# Sheet2.net
KiCad netlist of a schematic drawn in Altium Designer
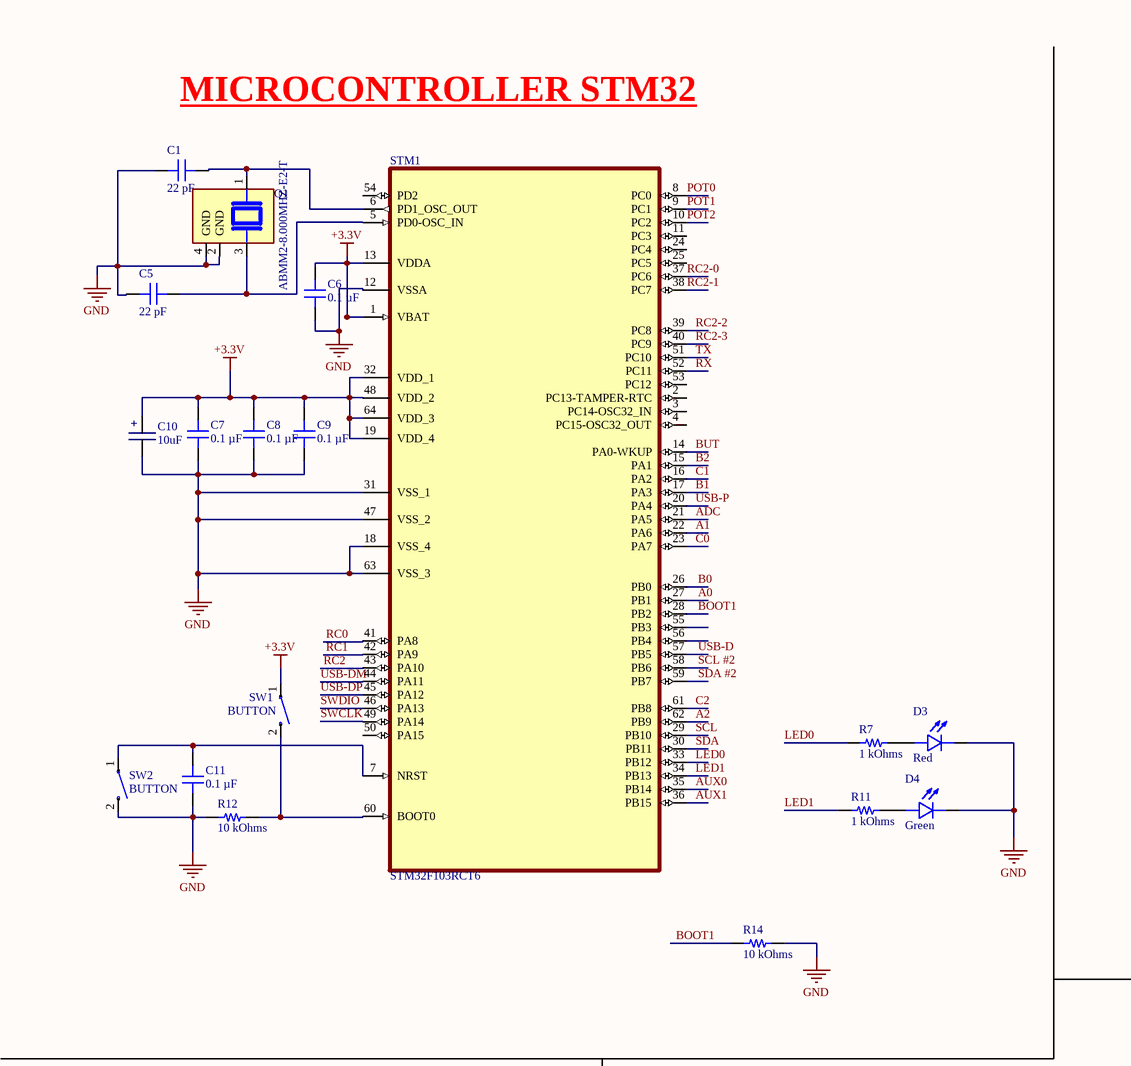
[diagram p0: Sheet2.SchDoc, top left]
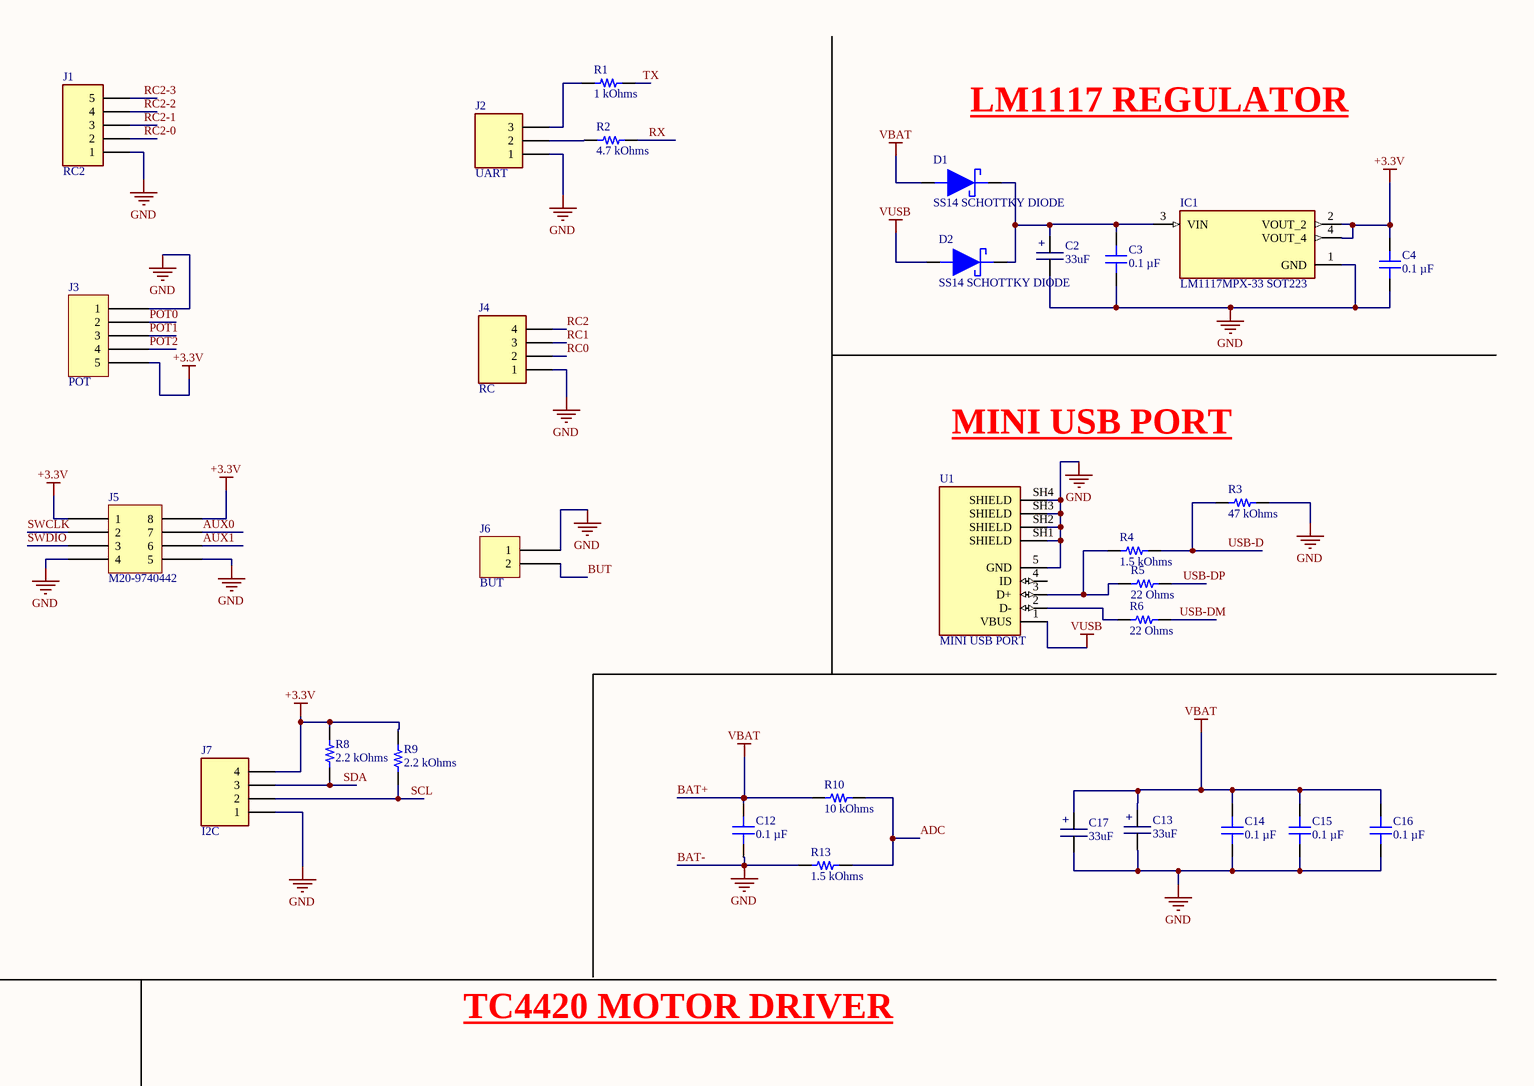
[diagram p1: Sheet2.SchDoc, top right]
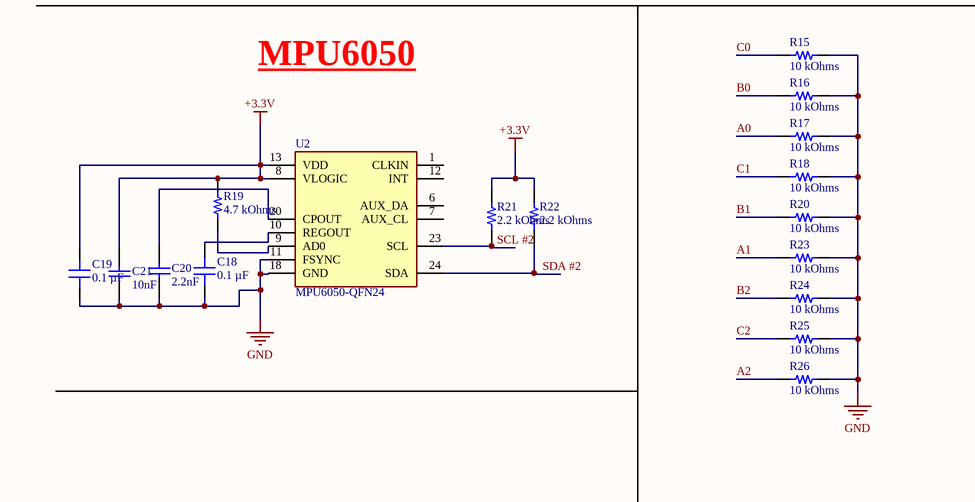
[diagram p2: Sheet2.SchDoc, bottom left]
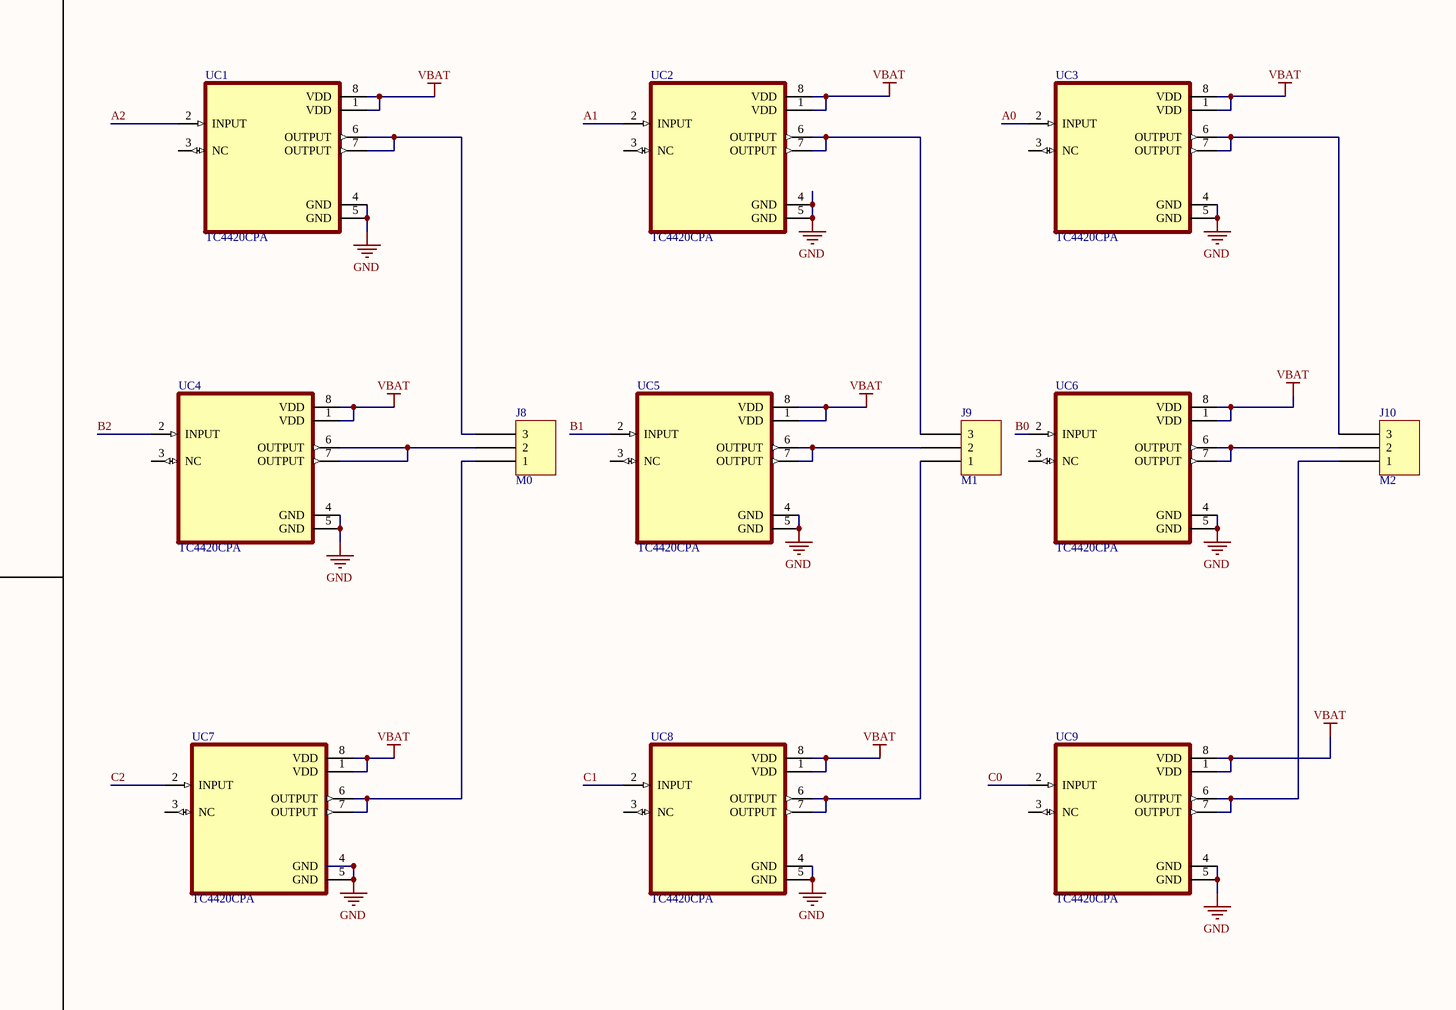
[diagram p3: Sheet2.SchDoc, bottom right]

(export (version "E")
  (design (tool "Eeschema 10.0.6"))
  (components
    (comp (ref "C1")
      (value "22 pF")
      (footprint "CAP 1206_3216 - 0.8MM")
      (description "CAP CER 22PF 50V C0G/NPO 1206")
      (fields
        (field (name "PART NUMBER") "CC1206JRNPO9BN220")
        (field (name "CAPACITANCE") "22 pF")
        (field (name "MANUFACTURER") "Yageo")
      )
      (libsource (lib "Celestial Altium Library - altium_library") (part "Capacitor"))
    )
    (comp (ref "C2")
      (value "33uF")
      (footprint "TANTAL CAP C-CASE")
      (libsource (lib "My_Library") (part "TANTAL CAP C-CASE"))
    )
    (comp (ref "C3")
      (value "0.1 µF")
      (footprint "CAP 1206_3216 - 0.8MM")
      (description "MLCC 1206 100V 100NF X7R")
      (fields
        (field (name "PART NUMBER") "1206B104J101N")
        (field (name "CAPACITANCE") "0.1 µF")
        (field (name "MANUFACTURER") "Knowles Novacap")
      )
      (libsource (lib "Celestial Altium Library - altium_library") (part "Capacitor"))
    )
    (comp (ref "C4")
      (value "0.1 µF")
      (footprint "CAP 1206_3216 - 0.8MM")
      (description "MLCC 1206 100V 100NF X7R")
      (fields
        (field (name "PART NUMBER") "1206B104J101N")
        (field (name "CAPACITANCE") "0.1 µF")
        (field (name "MANUFACTURER") "Knowles Novacap")
      )
      (libsource (lib "Celestial Altium Library - altium_library") (part "Capacitor"))
    )
    (comp (ref "C5")
      (value "22 pF")
      (footprint "CAP 1206_3216 - 0.8MM")
      (description "CAP CER 22PF 50V C0G/NPO 1206")
      (fields
        (field (name "PART NUMBER") "CC1206JRNPO9BN220")
        (field (name "CAPACITANCE") "22 pF")
        (field (name "MANUFACTURER") "Yageo")
      )
      (libsource (lib "Celestial Altium Library - altium_library") (part "Capacitor"))
    )
    (comp (ref "C6")
      (value "0.1 µF")
      (footprint "CAP 1206_3216 - 0.8MM")
      (description "MLCC 1206 100V 100NF X7R")
      (fields
        (field (name "PART NUMBER") "1206B104J101N")
        (field (name "CAPACITANCE") "0.1 µF")
        (field (name "MANUFACTURER") "Knowles Novacap")
      )
      (libsource (lib "Celestial Altium Library - altium_library") (part "Capacitor"))
    )
    (comp (ref "C7")
      (value "0.1 µF")
      (footprint "CAP 1206_3216 - 0.8MM")
      (description "MLCC 1206 100V 100NF X7R")
      (fields
        (field (name "PART NUMBER") "1206B104J101N")
        (field (name "CAPACITANCE") "0.1 µF")
        (field (name "MANUFACTURER") "Knowles Novacap")
      )
      (libsource (lib "Celestial Altium Library - altium_library") (part "Capacitor"))
    )
    (comp (ref "C8")
      (value "0.1 µF")
      (footprint "CAP 1206_3216 - 0.8MM")
      (description "MLCC 1206 100V 100NF X7R")
      (fields
        (field (name "PART NUMBER") "1206B104J101N")
        (field (name "CAPACITANCE") "0.1 µF")
        (field (name "MANUFACTURER") "Knowles Novacap")
      )
      (libsource (lib "Celestial Altium Library - altium_library") (part "Capacitor"))
    )
    (comp (ref "C9")
      (value "0.1 µF")
      (footprint "CAP 1206_3216 - 0.8MM")
      (description "MLCC 1206 100V 100NF X7R")
      (fields
        (field (name "PART NUMBER") "1206B104J101N")
        (field (name "CAPACITANCE") "0.1 µF")
        (field (name "MANUFACTURER") "Knowles Novacap")
      )
      (libsource (lib "Celestial Altium Library - altium_library") (part "Capacitor"))
    )
    (comp (ref "C10")
      (value "10uF")
      (footprint "TANTALUM SMD B")
      (description "Generic Tantalum Type B, 3.5x2.8x1.9.")
      (libsource (lib "Tantalum Capacitor") (part "TANTALUM SMD B"))
    )
    (comp (ref "C11")
      (value "0.1 µF")
      (footprint "CAP 1206_3216 - 0.8MM")
      (description "MLCC 1206 100V 100NF X7R")
      (fields
        (field (name "PART NUMBER") "1206B104J101N")
        (field (name "CAPACITANCE") "0.1 µF")
        (field (name "MANUFACTURER") "Knowles Novacap")
      )
      (libsource (lib "Celestial Altium Library - altium_library") (part "Capacitor"))
    )
    (comp (ref "C12")
      (value "0.1 µF")
      (footprint "CAP 1206_3216 - 0.8MM")
      (description "MLCC 1206 100V 100NF X7R")
      (fields
        (field (name "PART NUMBER") "1206B104J101N")
        (field (name "CAPACITANCE") "0.1 µF")
        (field (name "MANUFACTURER") "Knowles Novacap")
      )
      (libsource (lib "Celestial Altium Library - altium_library") (part "Capacitor"))
    )
    (comp (ref "C13")
      (value "33uF")
      (footprint "TANTAL CAP C-CASE")
      (libsource (lib "My_Library") (part "TANTAL CAP C-CASE"))
    )
    (comp (ref "C14")
      (value "0.1 µF")
      (footprint "CAP 1206_3216 - 0.8MM")
      (description "MLCC 1206 100V 100NF X7R")
      (fields
        (field (name "PART NUMBER") "1206B104J101N")
        (field (name "CAPACITANCE") "0.1 µF")
        (field (name "MANUFACTURER") "Knowles Novacap")
      )
      (libsource (lib "Celestial Altium Library - altium_library") (part "Capacitor"))
    )
    (comp (ref "C15")
      (value "0.1 µF")
      (footprint "CAP 1206_3216 - 0.8MM")
      (description "MLCC 1206 100V 100NF X7R")
      (fields
        (field (name "PART NUMBER") "1206B104J101N")
        (field (name "CAPACITANCE") "0.1 µF")
        (field (name "MANUFACTURER") "Knowles Novacap")
      )
      (libsource (lib "Celestial Altium Library - altium_library") (part "Capacitor"))
    )
    (comp (ref "C16")
      (value "0.1 µF")
      (footprint "CAP 1206_3216 - 0.8MM")
      (description "MLCC 1206 100V 100NF X7R")
      (fields
        (field (name "PART NUMBER") "1206B104J101N")
        (field (name "CAPACITANCE") "0.1 µF")
        (field (name "MANUFACTURER") "Knowles Novacap")
      )
      (libsource (lib "Celestial Altium Library - altium_library") (part "Capacitor"))
    )
    (comp (ref "C17")
      (value "33uF")
      (footprint "TANTAL CAP C-CASE")
      (libsource (lib "My_Library") (part "TANTAL CAP C-CASE"))
    )
    (comp (ref "C18")
      (value "0.1 µF")
      (footprint "CAP 1206_3216 - 0.8MM")
      (description "MLCC 1206 100V 100NF X7R")
      (fields
        (field (name "PART NUMBER") "1206B104J101N")
        (field (name "CAPACITANCE") "0.1 µF")
        (field (name "MANUFACTURER") "Knowles Novacap")
      )
      (libsource (lib "Celestial Altium Library - altium_library") (part "Capacitor"))
    )
    (comp (ref "C19")
      (value "0.1 µF")
      (footprint "CAP 1206_3216 - 0.8MM")
      (description "MLCC 1206 100V 100NF X7R")
      (fields
        (field (name "PART NUMBER") "1206B104J101N")
        (field (name "CAPACITANCE") "0.1 µF")
        (field (name "MANUFACTURER") "Knowles Novacap")
      )
      (libsource (lib "Celestial Altium Library - altium_library") (part "Capacitor"))
    )
    (comp (ref "C20")
      (value "2.2nF")
      (footprint "CAP1206")
      (fields
        (field (name "PART NUMBER") "CAP-SM-1206-X7R-10uF-50V")
        (field (name "MANUFACTURER") "GENERIC")
        (field (name "Comment") "CAP")
      )
      (libsource (lib "electronpowered") (part "CAP"))
    )
    (comp (ref "C21")
      (value "10nF")
      (footprint "CAP1206")
      (fields
        (field (name "PART NUMBER") "CAP-SM-1206-X7R-10uF-50V")
        (field (name "MANUFACTURER") "GENERIC")
        (field (name "Comment") "CAP")
      )
      (libsource (lib "electronpowered") (part "CAP"))
    )
    (comp (ref "D1")
      (value "SS14 SCHOTTKY DIODE")
      (footprint "SS14 SCHOTTKY DIODE")
      (libsource (lib "My_Library") (part "SS14 SCHOTTKY DIODE"))
    )
    (comp (ref "D2")
      (value "SS14 SCHOTTKY DIODE")
      (footprint "SS14 SCHOTTKY DIODE")
      (libsource (lib "My_Library") (part "SS14 SCHOTTKY DIODE"))
    )
    (comp (ref "D3")
      (value "Red")
      (footprint "LEDC3216X120N")
      (description "2.6 V Red LED SMD")
      (fields (field (name "MF") "Osram") (field (name "MP") "LHN974 RED LED 1206"))
      (libsource (lib "") (part "LHN974_RED_LED_1206_1"))
    )
    (comp (ref "D4")
      (value "Green")
      (footprint "LEDC3216X120N")
      (description "2.6 V Red LED SMD")
      (fields (field (name "MF") "Osram") (field (name "MP") "LHN974 RED LED 1206"))
      (libsource (lib "LHN974_RED_LED_1206") (part "LHN974_RED_LED_1206"))
    )
    (comp (ref "IC1")
      (value "LM1117MPX-33 SOT223")
      (footprint "LM1117MPX-33 SOT223")
      (libsource (lib "My_Library") (part "LM1117MPX-33 SOT223"))
    )
    (comp (ref "J1")
      (value "RC2")
      (footprint "header 5x1")
      (libsource (lib "My_Library") (part "header 5x1"))
    )
    (comp (ref "J2")
      (value "UART")
      (footprint "HEADER 3PIN")
      (libsource (lib "My_Library") (part "Header 3pin"))
    )
    (comp (ref "J3")
      (value "POT")
      (footprint "HARWIN M20-9960545")
      (description "CONN HEADER R/A 5POS 2.54MM")
      (fields (field (name "PART NUMBER") "M20-9960545") (field (name "MANUFACTURER") "Harwin Inc."))
      (libsource (lib "Celestial Altium Library - altium_library") (part "5 Pin"))
    )
    (comp (ref "J4")
      (value "RC")
      (footprint "Header 4pin")
      (libsource (lib "My_Library") (part "Header 4pin"))
    )
    (comp (ref "J5")
      (value "M20-9740442")
      (footprint "HARWIN M20-9740445")
      (description "CONN HEADER R/A 8POS 2.54MM")
      (fields (field (name "MANUFACTURER") "Harwin Inc."))
      (libsource (lib "Celestial Altium Library - altium_library") (part "2X4 PIN DU"))
    )
    (comp (ref "J6")
      (value "BUT")
      (footprint "HARWIN M20-9960245")
      (description "CONN HEADER R/A 2POS 2.54MM")
      (fields (field (name "PART NUMBER") "M20-9960245") (field (name "MANUFACTURER") "Harwin Inc."))
      (libsource (lib "Celestial Altium Library - altium_library") (part "2 Pin"))
    )
    (comp (ref "J7")
      (value "I2C")
      (footprint "Header 4pin")
      (libsource (lib "My_Library") (part "Header 4pin"))
    )
    (comp (ref "J8")
      (value "M0")
      (footprint "HARWIN M20-9960345")
      (description "CONN HEADER R/A 3POS 2.54MM")
      (fields (field (name "PART NUMBER") "M20-9960345") (field (name "MANUFACTURER") "Harwin Inc."))
      (libsource (lib "Celestial Altium Library - altium_library") (part "3 Pin"))
    )
    (comp (ref "J9")
      (value "M1")
      (footprint "HARWIN M20-9960345")
      (description "CONN HEADER R/A 3POS 2.54MM")
      (fields (field (name "PART NUMBER") "M20-9960345") (field (name "MANUFACTURER") "Harwin Inc."))
      (libsource (lib "Celestial Altium Library - altium_library") (part "3 Pin"))
    )
    (comp (ref "J10")
      (value "M2")
      (footprint "HARWIN M20-9960345")
      (description "CONN HEADER R/A 3POS 2.54MM")
      (fields (field (name "PART NUMBER") "M20-9960345") (field (name "MANUFACTURER") "Harwin Inc."))
      (libsource (lib "Celestial Altium Library - altium_library") (part "3 Pin"))
    )
    (comp (ref "Q1")
      (value "ABMM2-8.000MHZ-E2-T")
      (footprint "ABMM2-8.000MHZ-E2-T")
      (libsource (lib "My_Library") (part "ABMM2-8.000MHZ-E2-T"))
    )
    (comp (ref "R1")
      (value "1 kOhms")
      (footprint "RES 1206_3216")
      (description "RES 1K OHM 0.1% 1/8W 1206")
      (fields
        (field (name "PART NUMBER") "RNCS1206BKE1K00")
        (field (name "MANUFACTURER") "Stackpole Electronics Inc")
      )
      (libsource (lib "Celestial Altium Library - altium_library") (part "Resistor"))
    )
    (comp (ref "R2")
      (value "4.7 kOhms")
      (footprint "RES 1206_3216")
      (description "RES SMD 4.7K OHM 1% 1/4W 1206")
      (fields
        (field (name "PART NUMBER") "CRG1206F4K7")
        (field (name "MANUFACTURER") "TE Connectivity Passive Product")
      )
      (libsource (lib "Celestial Altium Library - altium_library") (part "Resistor"))
    )
    (comp (ref "R3")
      (value "47 kOhms")
      (footprint "YAGEO RES 1206_3216")
      (description "RES 47K OHM 5% 1/4W 1206")
      (fields (field (name "PART NUMBER") "RC1206JR-0747KL") (field (name "MANUFACTURER") "Yageo"))
      (libsource (lib "Celestial Altium Library - altium_library") (part "Resistor"))
    )
    (comp (ref "R4")
      (value "1.5 kOhms")
      (footprint "RES 1206_3216")
      (description "RES 1.5K OHM 1% 1/2W 1206")
      (fields
        (field (name "PART NUMBER") "RNCP1206FTD1K50")
        (field (name "MANUFACTURER") "Stackpole Electronics Inc")
      )
      (libsource (lib "Celestial Altium Library - altium_library") (part "Resistor"))
    )
    (comp (ref "R5")
      (value "22 Ohms")
      (footprint "YAGEO RES 1206_3216")
      (description "RES SMD 22 OHM 5% 1/4W 1206")
      (fields (field (name "PART NUMBER") "AC1206JR-0722RL") (field (name "MANUFACTURER") "Yageo"))
      (libsource (lib "Celestial Altium Library - altium_library") (part "Resistor"))
    )
    (comp (ref "R6")
      (value "22 Ohms")
      (footprint "YAGEO RES 1206_3216")
      (description "RES SMD 22 OHM 5% 1/4W 1206")
      (fields (field (name "PART NUMBER") "AC1206JR-0722RL") (field (name "MANUFACTURER") "Yageo"))
      (libsource (lib "Celestial Altium Library - altium_library") (part "Resistor"))
    )
    (comp (ref "R7")
      (value "1 kOhms")
      (footprint "RES 1206_3216")
      (description "RES 1K OHM 0.1% 1/8W 1206")
      (fields
        (field (name "PART NUMBER") "RNCS1206BKE1K00")
        (field (name "MANUFACTURER") "Stackpole Electronics Inc")
      )
      (libsource (lib "Celestial Altium Library - altium_library") (part "Resistor"))
    )
    (comp (ref "R8")
      (value "2.2 kOhms")
      (footprint "YAGEO RES 1206_3216")
      (description "RES SMD 2.2K OHM 0.1% 1/4W 1206")
      (fields (field (name "PART NUMBER") "RT1206BRD072K2L") (field (name "MANUFACTURER") "Yageo"))
      (libsource (lib "Celestial Altium Library - altium_library") (part "Resistor"))
    )
    (comp (ref "R9")
      (value "2.2 kOhms")
      (footprint "YAGEO RES 1206_3216")
      (description "RES SMD 2.2K OHM 0.1% 1/4W 1206")
      (fields (field (name "PART NUMBER") "RT1206BRD072K2L") (field (name "MANUFACTURER") "Yageo"))
      (libsource (lib "Celestial Altium Library - altium_library") (part "Resistor"))
    )
    (comp (ref "R10")
      (value "10 kOhms")
      (footprint "RES 1206_3216")
      (description "RES SMD 10K OHM 1% 1/4W 1206")
      (fields
        (field (name "PART NUMBER") "CRG1206F10K")
        (field (name "MANUFACTURER") "TE Connectivity Passive Product")
      )
      (libsource (lib "Celestial Altium Library - altium_library") (part "Resistor"))
    )
    (comp (ref "R11")
      (value "1 kOhms")
      (footprint "RES 1206_3216")
      (description "RES 1K OHM 0.1% 1/8W 1206")
      (fields
        (field (name "PART NUMBER") "RNCS1206BKE1K00")
        (field (name "MANUFACTURER") "Stackpole Electronics Inc")
      )
      (libsource (lib "Celestial Altium Library - altium_library") (part "Resistor"))
    )
    (comp (ref "R12")
      (value "10 kOhms")
      (footprint "RES 1206_3216")
      (description "RES SMD 10K OHM 1% 1/4W 1206")
      (fields
        (field (name "PART NUMBER") "CRG1206F10K")
        (field (name "MANUFACTURER") "TE Connectivity Passive Product")
      )
      (libsource (lib "Celestial Altium Library - altium_library") (part "Resistor"))
    )
    (comp (ref "R13")
      (value "1.5 kOhms")
      (footprint "RES 1206_3216")
      (description "RES 1.5K OHM 1% 1/2W 1206")
      (fields
        (field (name "PART NUMBER") "RNCP1206FTD1K50")
        (field (name "MANUFACTURER") "Stackpole Electronics Inc")
      )
      (libsource (lib "Celestial Altium Library - altium_library") (part "Resistor"))
    )
    (comp (ref "R14")
      (value "10 kOhms")
      (footprint "RES 1206_3216")
      (description "RES SMD 10K OHM 1% 1/4W 1206")
      (fields
        (field (name "PART NUMBER") "CRG1206F10K")
        (field (name "MANUFACTURER") "TE Connectivity Passive Product")
      )
      (libsource (lib "Celestial Altium Library - altium_library") (part "Resistor"))
    )
    (comp (ref "R15")
      (value "10 kOhms")
      (footprint "RES 1206_3216")
      (description "RES SMD 10K OHM 1% 1/4W 1206")
      (fields
        (field (name "PART NUMBER") "CRG1206F10K")
        (field (name "MANUFACTURER") "TE Connectivity Passive Product")
      )
      (libsource (lib "Celestial Altium Library - altium_library") (part "Resistor"))
    )
    (comp (ref "R16")
      (value "10 kOhms")
      (footprint "RES 1206_3216")
      (description "RES SMD 10K OHM 1% 1/4W 1206")
      (fields
        (field (name "PART NUMBER") "CRG1206F10K")
        (field (name "MANUFACTURER") "TE Connectivity Passive Product")
      )
      (libsource (lib "Celestial Altium Library - altium_library") (part "Resistor"))
    )
    (comp (ref "R17")
      (value "10 kOhms")
      (footprint "RES 1206_3216")
      (description "RES SMD 10K OHM 1% 1/4W 1206")
      (fields
        (field (name "PART NUMBER") "CRG1206F10K")
        (field (name "MANUFACTURER") "TE Connectivity Passive Product")
      )
      (libsource (lib "Celestial Altium Library - altium_library") (part "Resistor"))
    )
    (comp (ref "R18")
      (value "10 kOhms")
      (footprint "RES 1206_3216")
      (description "RES SMD 10K OHM 1% 1/4W 1206")
      (fields
        (field (name "PART NUMBER") "CRG1206F10K")
        (field (name "MANUFACTURER") "TE Connectivity Passive Product")
      )
      (libsource (lib "Celestial Altium Library - altium_library") (part "Resistor"))
    )
    (comp (ref "R19")
      (value "4.7 kOhms")
      (footprint "RES 1206_3216")
      (description "RES SMD 4.7K OHM 1% 1/4W 1206")
      (fields
        (field (name "PART NUMBER") "CRG1206F4K7")
        (field (name "MANUFACTURER") "TE Connectivity Passive Product")
      )
      (libsource (lib "Celestial Altium Library - altium_library") (part "Resistor"))
    )
    (comp (ref "R20")
      (value "10 kOhms")
      (footprint "RES 1206_3216")
      (description "RES SMD 10K OHM 1% 1/4W 1206")
      (fields
        (field (name "PART NUMBER") "CRG1206F10K")
        (field (name "MANUFACTURER") "TE Connectivity Passive Product")
      )
      (libsource (lib "Celestial Altium Library - altium_library") (part "Resistor"))
    )
    (comp (ref "R21")
      (value "2.2 kOhms")
      (footprint "YAGEO RES 1206_3216")
      (description "RES SMD 2.2K OHM 0.1% 1/4W 1206")
      (fields (field (name "PART NUMBER") "RT1206BRD072K2L") (field (name "MANUFACTURER") "Yageo"))
      (libsource (lib "Celestial Altium Library - altium_library") (part "Resistor"))
    )
    (comp (ref "R22")
      (value "2.2 kOhms")
      (footprint "YAGEO RES 1206_3216")
      (description "RES SMD 2.2K OHM 0.1% 1/4W 1206")
      (fields (field (name "PART NUMBER") "RT1206BRD072K2L") (field (name "MANUFACTURER") "Yageo"))
      (libsource (lib "Celestial Altium Library - altium_library") (part "Resistor"))
    )
    (comp (ref "R23")
      (value "10 kOhms")
      (footprint "RES 1206_3216")
      (description "RES SMD 10K OHM 1% 1/4W 1206")
      (fields
        (field (name "PART NUMBER") "CRG1206F10K")
        (field (name "MANUFACTURER") "TE Connectivity Passive Product")
      )
      (libsource (lib "Celestial Altium Library - altium_library") (part "Resistor"))
    )
    (comp (ref "R24")
      (value "10 kOhms")
      (footprint "RES 1206_3216")
      (description "RES SMD 10K OHM 1% 1/4W 1206")
      (fields
        (field (name "PART NUMBER") "CRG1206F10K")
        (field (name "MANUFACTURER") "TE Connectivity Passive Product")
      )
      (libsource (lib "Celestial Altium Library - altium_library") (part "Resistor"))
    )
    (comp (ref "R25")
      (value "10 kOhms")
      (footprint "RES 1206_3216")
      (description "RES SMD 10K OHM 1% 1/4W 1206")
      (fields
        (field (name "PART NUMBER") "CRG1206F10K")
        (field (name "MANUFACTURER") "TE Connectivity Passive Product")
      )
      (libsource (lib "Celestial Altium Library - altium_library") (part "Resistor"))
    )
    (comp (ref "R26")
      (value "10 kOhms")
      (footprint "RES 1206_3216")
      (description "RES SMD 10K OHM 1% 1/4W 1206")
      (fields
        (field (name "PART NUMBER") "CRG1206F10K")
        (field (name "MANUFACTURER") "TE Connectivity Passive Product")
      )
      (libsource (lib "Celestial Altium Library - altium_library") (part "Resistor"))
    )
    (comp (ref "STM1")
      (value "STM32F103RCT6")
      (footprint "STM32F103RCT6")
      (libsource (lib "My_Library") (part "STM32F103RCT6"))
    )
    (comp (ref "SW1")
      (value "BUTTON")
      (footprint "SW_1437566-3")
      (libsource (lib "My_Library") (part "RESET_BUTTON"))
    )
    (comp (ref "SW2")
      (value "BUTTON")
      (footprint "SW_1437566-3")
      (libsource (lib "My_Library") (part "RESET_BUTTON"))
    )
    (comp (ref "U1")
      (value "MINI USB PORT")
      (footprint "MINI USB PORT")
      (libsource (lib "My_Library") (part "MINI USB PORT"))
    )
    (comp (ref "U2")
      (value "MPU6050-QFN24")
      (footprint "MPU6050-QFN24")
      (libsource (lib "My_Library") (part "MPU6050-QFN24"))
    )
    (comp (ref "UC1")
      (value "TC4420CPA")
      (footprint "TC4420CPA")
      (libsource (lib "My_Library") (part "TC4420CPA"))
    )
    (comp (ref "UC2")
      (value "TC4420CPA")
      (footprint "TC4420CPA")
      (libsource (lib "My_Library") (part "TC4420CPA"))
    )
    (comp (ref "UC3")
      (value "TC4420CPA")
      (footprint "TC4420CPA")
      (libsource (lib "My_Library") (part "TC4420CPA"))
    )
    (comp (ref "UC4")
      (value "TC4420CPA")
      (footprint "TC4420CPA")
      (libsource (lib "My_Library") (part "TC4420CPA"))
    )
    (comp (ref "UC5")
      (value "TC4420CPA")
      (footprint "TC4420CPA")
      (libsource (lib "My_Library") (part "TC4420CPA"))
    )
    (comp (ref "UC6")
      (value "TC4420CPA")
      (footprint "TC4420CPA")
      (libsource (lib "My_Library") (part "TC4420CPA"))
    )
    (comp (ref "UC7")
      (value "TC4420CPA")
      (footprint "TC4420CPA")
      (libsource (lib "My_Library") (part "TC4420CPA"))
    )
    (comp (ref "UC8")
      (value "TC4420CPA")
      (footprint "TC4420CPA")
      (libsource (lib "My_Library") (part "TC4420CPA"))
    )
    (comp (ref "UC9")
      (value "TC4420CPA")
      (footprint "TC4420CPA")
      (libsource (lib "My_Library") (part "TC4420CPA"))
    )
  )
  (nets
    (net (code "1") (name "+3.3V") (class "Default")
      (node (ref "C10") (pin "2") (pinfunction "2_2") (pintype "passive"))
      (node (ref "C19") (pin "1") (pinfunction "1_1") (pintype "passive"))
      (node (ref "C21") (pin "2") (pinfunction "2_2") (pintype "passive"))
      (node (ref "C4") (pin "1") (pinfunction "1_1") (pintype "passive"))
      (node (ref "C6") (pin "1") (pinfunction "1_1") (pintype "passive"))
      (node (ref "C7") (pin "1") (pinfunction "1_1") (pintype "passive"))
      (node (ref "C8") (pin "1") (pinfunction "1_1") (pintype "passive"))
      (node (ref "C9") (pin "1") (pinfunction "1_1") (pintype "passive"))
      (node (ref "IC1") (pin "2") (pinfunction "VOUT_2_2") (pintype "output"))
      (node (ref "IC1") (pin "4") (pinfunction "VOUT_4_4") (pintype "output"))
      (node (ref "J3") (pin "5") (pinfunction "5_5") (pintype "passive"))
      (node (ref "J5") (pin "1") (pinfunction "1_1") (pintype "passive"))
      (node (ref "J5") (pin "8") (pinfunction "8_8") (pintype "passive"))
      (node (ref "J7") (pin "04") (pinfunction "4_04") (pintype "passive"))
      (node (ref "R19") (pin "1") (pinfunction "1_1") (pintype "passive"))
      (node (ref "R21") (pin "1") (pinfunction "1_1") (pintype "passive"))
      (node (ref "R22") (pin "1") (pinfunction "1_1") (pintype "passive"))
      (node (ref "R8") (pin "1") (pinfunction "1_1") (pintype "passive"))
      (node (ref "R9") (pin "2") (pinfunction "2_2") (pintype "passive"))
      (node (ref "STM1") (pin "1") (pinfunction "VBAT_1") (pintype "input"))
      (node (ref "STM1") (pin "13") (pinfunction "VDDA_13") (pintype "power_in"))
      (node (ref "STM1") (pin "19") (pinfunction "VDD_4_19") (pintype "power_in"))
      (node (ref "STM1") (pin "32") (pinfunction "VDD_1_32") (pintype "power_in"))
      (node (ref "STM1") (pin "48") (pinfunction "VDD_2_48") (pintype "power_in"))
      (node (ref "STM1") (pin "64") (pinfunction "VDD_3_64") (pintype "power_in"))
      (node (ref "SW1") (pin "1") (pinfunction "1_1") (pintype "passive"))
      (node (ref "U2") (pin "13") (pinfunction "VDD_13") (pintype "passive"))
      (node (ref "U2") (pin "8") (pinfunction "VLOGIC_8") (pintype "passive"))
    )
    (net (code "3") (name "/A0") (class "Default")
      (node (ref "R17") (pin "1") (pinfunction "1_1") (pintype "passive"))
      (node (ref "STM1") (pin "27") (pinfunction "PB1_27") (pintype "bidirectional"))
      (node (ref "UC3") (pin "2") (pinfunction "INPUT_2") (pintype "input"))
    )
    (net (code "4") (name "/A1") (class "Default")
      (node (ref "R23") (pin "1") (pinfunction "1_1") (pintype "passive"))
      (node (ref "STM1") (pin "22") (pinfunction "PA6_22") (pintype "bidirectional"))
      (node (ref "UC2") (pin "2") (pinfunction "INPUT_2") (pintype "input"))
    )
    (net (code "5") (name "/A2") (class "Default")
      (node (ref "R26") (pin "1") (pinfunction "1_1") (pintype "passive"))
      (node (ref "STM1") (pin "62") (pinfunction "PB9_62") (pintype "bidirectional"))
      (node (ref "UC1") (pin "2") (pinfunction "INPUT_2") (pintype "input"))
    )
    (net (code "6") (name "/ADC") (class "Default")
      (node (ref "R10") (pin "2") (pinfunction "2_2") (pintype "passive"))
      (node (ref "R13") (pin "2") (pinfunction "2_2") (pintype "passive"))
      (node (ref "STM1") (pin "21") (pinfunction "PA5_21") (pintype "bidirectional"))
    )
    (net (code "7") (name "/AUX0") (class "Default")
      (node (ref "J5") (pin "7") (pinfunction "7_7") (pintype "passive"))
      (node (ref "STM1") (pin "35") (pinfunction "PB14_35") (pintype "bidirectional"))
    )
    (net (code "8") (name "/AUX1") (class "Default")
      (node (ref "J5") (pin "6") (pinfunction "6_6") (pintype "passive"))
      (node (ref "STM1") (pin "36") (pinfunction "PB15_36") (pintype "bidirectional"))
    )
    (net (code "9") (name "/B0") (class "Default")
      (node (ref "R16") (pin "1") (pinfunction "1_1") (pintype "passive"))
      (node (ref "STM1") (pin "26") (pinfunction "PB0_26") (pintype "bidirectional"))
      (node (ref "UC6") (pin "2") (pinfunction "INPUT_2") (pintype "input"))
    )
    (net (code "10") (name "/B1") (class "Default")
      (node (ref "R20") (pin "1") (pinfunction "1_1") (pintype "passive"))
      (node (ref "STM1") (pin "17") (pinfunction "PA3_17") (pintype "bidirectional"))
      (node (ref "UC5") (pin "2") (pinfunction "INPUT_2") (pintype "input"))
    )
    (net (code "11") (name "/B2") (class "Default")
      (node (ref "R24") (pin "1") (pinfunction "1_1") (pintype "passive"))
      (node (ref "STM1") (pin "15") (pinfunction "PA1_15") (pintype "bidirectional"))
      (node (ref "UC4") (pin "2") (pinfunction "INPUT_2") (pintype "input"))
    )
    (net (code "12") (name "/BOOT1") (class "Default")
      (node (ref "R14") (pin "1") (pinfunction "1_1") (pintype "passive"))
      (node (ref "STM1") (pin "28") (pinfunction "PB2_28") (pintype "bidirectional"))
    )
    (net (code "13") (name "/BUT") (class "Default")
      (node (ref "J6") (pin "2") (pinfunction "2_2") (pintype "passive"))
      (node (ref "STM1") (pin "14") (pinfunction "PA0-WKUP_14") (pintype "bidirectional"))
    )
    (net (code "14") (name "/C0") (class "Default")
      (node (ref "R15") (pin "1") (pinfunction "1_1") (pintype "passive"))
      (node (ref "STM1") (pin "23") (pinfunction "PA7_23") (pintype "bidirectional"))
      (node (ref "UC9") (pin "2") (pinfunction "INPUT_2") (pintype "input"))
    )
    (net (code "15") (name "/C1") (class "Default")
      (node (ref "R18") (pin "1") (pinfunction "1_1") (pintype "passive"))
      (node (ref "STM1") (pin "16") (pinfunction "PA2_16") (pintype "bidirectional"))
      (node (ref "UC8") (pin "2") (pinfunction "INPUT_2") (pintype "input"))
    )
    (net (code "16") (name "/C2") (class "Default")
      (node (ref "R25") (pin "1") (pinfunction "1_1") (pintype "passive"))
      (node (ref "STM1") (pin "61") (pinfunction "PB8_61") (pintype "bidirectional"))
      (node (ref "UC7") (pin "2") (pinfunction "INPUT_2") (pintype "input"))
    )
    (net (code "17") (name "/LED0") (class "Default")
      (node (ref "R7") (pin "1") (pinfunction "1_1") (pintype "passive"))
      (node (ref "STM1") (pin "33") (pinfunction "PB12_33") (pintype "bidirectional"))
    )
    (net (code "18") (name "/LED1") (class "Default")
      (node (ref "R11") (pin "1") (pinfunction "1_1") (pintype "passive"))
      (node (ref "STM1") (pin "34") (pinfunction "PB13_34") (pintype "bidirectional"))
    )
    (net (code "19") (name "/POT0") (class "Default")
      (node (ref "J3") (pin "2") (pinfunction "2_2") (pintype "passive"))
      (node (ref "STM1") (pin "8") (pinfunction "PC0_8") (pintype "bidirectional"))
    )
    (net (code "20") (name "/POT1") (class "Default")
      (node (ref "J3") (pin "3") (pinfunction "3_3") (pintype "passive"))
      (node (ref "STM1") (pin "9") (pinfunction "PC1_9") (pintype "bidirectional"))
    )
    (net (code "21") (name "/POT2") (class "Default")
      (node (ref "J3") (pin "4") (pinfunction "4_4") (pintype "passive"))
      (node (ref "STM1") (pin "10") (pinfunction "PC2_10") (pintype "bidirectional"))
    )
    (net (code "22") (name "/RC0") (class "Default")
      (node (ref "J4") (pin "02") (pinfunction "2_02") (pintype "passive"))
      (node (ref "STM1") (pin "41") (pinfunction "PA8_41") (pintype "bidirectional"))
    )
    (net (code "23") (name "/RC1") (class "Default")
      (node (ref "J4") (pin "03") (pinfunction "3_03") (pintype "passive"))
      (node (ref "STM1") (pin "42") (pinfunction "PA9_42") (pintype "bidirectional"))
    )
    (net (code "24") (name "/RC2") (class "Default")
      (node (ref "J4") (pin "04") (pinfunction "4_04") (pintype "passive"))
      (node (ref "STM1") (pin "43") (pinfunction "PA10_43") (pintype "bidirectional"))
    )
    (net (code "25") (name "/RC2-0") (class "Default")
      (node (ref "J1") (pin "2") (pinfunction "2_2") (pintype "passive"))
      (node (ref "STM1") (pin "37") (pinfunction "PC6_37") (pintype "bidirectional"))
    )
    (net (code "26") (name "/RC2-1") (class "Default")
      (node (ref "J1") (pin "3") (pinfunction "3_3") (pintype "passive"))
      (node (ref "STM1") (pin "38") (pinfunction "PC7_38") (pintype "bidirectional"))
    )
    (net (code "27") (name "/RC2-2") (class "Default")
      (node (ref "J1") (pin "4") (pinfunction "4_4") (pintype "passive"))
      (node (ref "STM1") (pin "39") (pinfunction "PC8_39") (pintype "bidirectional"))
    )
    (net (code "28") (name "/RC2-3") (class "Default")
      (node (ref "J1") (pin "5") (pinfunction "5_5") (pintype "passive"))
      (node (ref "STM1") (pin "40") (pinfunction "PC9_40") (pintype "bidirectional"))
    )
    (net (code "29") (name "/RX") (class "Default")
      (node (ref "R2") (pin "2") (pinfunction "2_2") (pintype "passive"))
      (node (ref "STM1") (pin "52") (pinfunction "PC11_52") (pintype "bidirectional"))
    )
    (net (code "30") (name "/SCL") (class "Default")
      (node (ref "J7") (pin "02") (pinfunction "2_02") (pintype "passive"))
      (node (ref "R9") (pin "1") (pinfunction "1_1") (pintype "passive"))
      (node (ref "STM1") (pin "29") (pinfunction "PB10_29") (pintype "bidirectional"))
    )
    (net (code "31") (name "/SCL #2") (class "Default")
      (node (ref "R21") (pin "2") (pinfunction "2_2") (pintype "passive"))
      (node (ref "STM1") (pin "58") (pinfunction "PB6_58") (pintype "bidirectional"))
      (node (ref "U2") (pin "23") (pinfunction "SCL_23") (pintype "passive"))
    )
    (net (code "32") (name "/SDA") (class "Default")
      (node (ref "J7") (pin "03") (pinfunction "3_03") (pintype "passive"))
      (node (ref "R8") (pin "2") (pinfunction "2_2") (pintype "passive"))
      (node (ref "STM1") (pin "30") (pinfunction "PB11_30") (pintype "bidirectional"))
    )
    (net (code "33") (name "/SDA #2") (class "Default")
      (node (ref "R22") (pin "2") (pinfunction "2_2") (pintype "passive"))
      (node (ref "STM1") (pin "59") (pinfunction "PB7_59") (pintype "bidirectional"))
      (node (ref "U2") (pin "24") (pinfunction "SDA_24") (pintype "passive"))
    )
    (net (code "34") (name "/SWCLK") (class "Default")
      (node (ref "J5") (pin "2") (pinfunction "2_2") (pintype "passive"))
      (node (ref "STM1") (pin "49") (pinfunction "PA14_49") (pintype "bidirectional"))
    )
    (net (code "35") (name "/SWDIO") (class "Default")
      (node (ref "J5") (pin "3") (pinfunction "3_3") (pintype "passive"))
      (node (ref "STM1") (pin "46") (pinfunction "PA13_46") (pintype "bidirectional"))
    )
    (net (code "36") (name "/TX") (class "Default")
      (node (ref "R1") (pin "2") (pinfunction "2_2") (pintype "passive"))
      (node (ref "STM1") (pin "51") (pinfunction "PC10_51") (pintype "bidirectional"))
    )
    (net (code "37") (name "/USB-D") (class "Default")
      (node (ref "R3") (pin "1") (pinfunction "1_1") (pintype "passive"))
      (node (ref "R4") (pin "2") (pinfunction "2_2") (pintype "passive"))
      (node (ref "STM1") (pin "57") (pinfunction "PB5_57") (pintype "bidirectional"))
    )
    (net (code "38") (name "/USB-DM") (class "Default")
      (node (ref "R6") (pin "2") (pinfunction "2_2") (pintype "passive"))
      (node (ref "STM1") (pin "44") (pinfunction "PA11_44") (pintype "bidirectional"))
    )
    (net (code "39") (name "/USB-DP") (class "Default")
      (node (ref "R5") (pin "2") (pinfunction "2_2") (pintype "passive"))
      (node (ref "STM1") (pin "45") (pinfunction "PA12_45") (pintype "bidirectional"))
    )
    (net (code "40") (name "/USB-P") (class "Default")
      (node (ref "STM1") (pin "20") (pinfunction "PA4_20") (pintype "bidirectional"))
    )
    (net (code "41") (name "GND") (class "Default")
      (node (ref "C1") (pin "1") (pinfunction "1_1") (pintype "passive"))
      (node (ref "C10") (pin "1") (pinfunction "1_1") (pintype "passive"))
      (node (ref "C11") (pin "2") (pinfunction "2_2") (pintype "passive"))
      (node (ref "C12") (pin "2") (pinfunction "2_2") (pintype "passive"))
      (node (ref "C13") (pin "1") (pinfunction "1_1") (pintype "passive"))
      (node (ref "C14") (pin "2") (pinfunction "2_2") (pintype "passive"))
      (node (ref "C15") (pin "2") (pinfunction "2_2") (pintype "passive"))
      (node (ref "C16") (pin "2") (pinfunction "2_2") (pintype "passive"))
      (node (ref "C17") (pin "1") (pinfunction "1_1") (pintype "passive"))
      (node (ref "C18") (pin "2") (pinfunction "2_2") (pintype "passive"))
      (node (ref "C19") (pin "2") (pinfunction "2_2") (pintype "passive"))
      (node (ref "C2") (pin "1") (pinfunction "1_1") (pintype "passive"))
      (node (ref "C20") (pin "1") (pinfunction "1_1") (pintype "passive"))
      (node (ref "C21") (pin "1") (pinfunction "1_1") (pintype "passive"))
      (node (ref "C3") (pin "2") (pinfunction "2_2") (pintype "passive"))
      (node (ref "C4") (pin "2") (pinfunction "2_2") (pintype "passive"))
      (node (ref "C5") (pin "1") (pinfunction "1_1") (pintype "passive"))
      (node (ref "C6") (pin "2") (pinfunction "2_2") (pintype "passive"))
      (node (ref "C7") (pin "2") (pinfunction "2_2") (pintype "passive"))
      (node (ref "C8") (pin "2") (pinfunction "2_2") (pintype "passive"))
      (node (ref "C9") (pin "2") (pinfunction "2_2") (pintype "passive"))
      (node (ref "D3") (pin "NEG") (pinfunction "NEG_NEG") (pintype "passive"))
      (node (ref "D4") (pin "NEG") (pinfunction "NEG_NEG") (pintype "passive"))
      (node (ref "IC1") (pin "1") (pinfunction "GND_1") (pintype "power_in"))
      (node (ref "J1") (pin "1") (pinfunction "1_1") (pintype "passive"))
      (node (ref "J2") (pin "1") (pinfunction "1_1") (pintype "passive"))
      (node (ref "J3") (pin "1") (pinfunction "1_1") (pintype "passive"))
      (node (ref "J4") (pin "01") (pinfunction "1_01") (pintype "passive"))
      (node (ref "J5") (pin "4") (pinfunction "4_4") (pintype "passive"))
      (node (ref "J5") (pin "5") (pinfunction "5_5") (pintype "passive"))
      (node (ref "J6") (pin "1") (pinfunction "1_1") (pintype "passive"))
      (node (ref "J7") (pin "01") (pinfunction "1_01") (pintype "passive"))
      (node (ref "Q1") (pin "2") (pinfunction "GND_2") (pintype "power_in"))
      (node (ref "Q1") (pin "4") (pinfunction "GND_4") (pintype "power_in"))
      (node (ref "R12") (pin "1") (pinfunction "1_1") (pintype "passive"))
      (node (ref "R13") (pin "1") (pinfunction "1_1") (pintype "passive"))
      (node (ref "R14") (pin "2") (pinfunction "2_2") (pintype "passive"))
      (node (ref "R15") (pin "2") (pinfunction "2_2") (pintype "passive"))
      (node (ref "R16") (pin "2") (pinfunction "2_2") (pintype "passive"))
      (node (ref "R17") (pin "2") (pinfunction "2_2") (pintype "passive"))
      (node (ref "R18") (pin "2") (pinfunction "2_2") (pintype "passive"))
      (node (ref "R20") (pin "2") (pinfunction "2_2") (pintype "passive"))
      (node (ref "R23") (pin "2") (pinfunction "2_2") (pintype "passive"))
      (node (ref "R24") (pin "2") (pinfunction "2_2") (pintype "passive"))
      (node (ref "R25") (pin "2") (pinfunction "2_2") (pintype "passive"))
      (node (ref "R26") (pin "2") (pinfunction "2_2") (pintype "passive"))
      (node (ref "R3") (pin "2") (pinfunction "2_2") (pintype "passive"))
      (node (ref "STM1") (pin "12") (pinfunction "VSSA_12") (pintype "power_in"))
      (node (ref "STM1") (pin "18") (pinfunction "VSS_4_18") (pintype "power_in"))
      (node (ref "STM1") (pin "31") (pinfunction "VSS_1_31") (pintype "power_in"))
      (node (ref "STM1") (pin "47") (pinfunction "VSS_2_47") (pintype "power_in"))
      (node (ref "STM1") (pin "63") (pinfunction "VSS_3_63") (pintype "power_in"))
      (node (ref "SW2") (pin "2") (pinfunction "2_2") (pintype "passive"))
      (node (ref "U1") (pin "5") (pinfunction "GND_5") (pintype "power_in"))
      (node (ref "U1") (pin "SH1") (pinfunction "SHIELD_SH1") (pintype "passive"))
      (node (ref "U1") (pin "SH2") (pinfunction "SHIELD_SH2") (pintype "passive"))
      (node (ref "U1") (pin "SH3") (pinfunction "SHIELD_SH3") (pintype "passive"))
      (node (ref "U1") (pin "SH4") (pinfunction "SHIELD_SH4") (pintype "passive"))
      (node (ref "U2") (pin "11") (pinfunction "FSYNC_11") (pintype "passive"))
      (node (ref "U2") (pin "18") (pinfunction "GND_18") (pintype "passive"))
      (node (ref "UC1") (pin "4") (pinfunction "GND_4") (pintype "power_in"))
      (node (ref "UC1") (pin "5") (pinfunction "GND_5") (pintype "power_in"))
      (node (ref "UC2") (pin "4") (pinfunction "GND_4") (pintype "power_in"))
      (node (ref "UC2") (pin "5") (pinfunction "GND_5") (pintype "power_in"))
      (node (ref "UC3") (pin "4") (pinfunction "GND_4") (pintype "power_in"))
      (node (ref "UC3") (pin "5") (pinfunction "GND_5") (pintype "power_in"))
      (node (ref "UC4") (pin "4") (pinfunction "GND_4") (pintype "power_in"))
      (node (ref "UC4") (pin "5") (pinfunction "GND_5") (pintype "power_in"))
      (node (ref "UC5") (pin "4") (pinfunction "GND_4") (pintype "power_in"))
      (node (ref "UC5") (pin "5") (pinfunction "GND_5") (pintype "power_in"))
      (node (ref "UC6") (pin "4") (pinfunction "GND_4") (pintype "power_in"))
      (node (ref "UC6") (pin "5") (pinfunction "GND_5") (pintype "power_in"))
      (node (ref "UC7") (pin "4") (pinfunction "GND_4") (pintype "power_in"))
      (node (ref "UC7") (pin "5") (pinfunction "GND_5") (pintype "power_in"))
      (node (ref "UC8") (pin "4") (pinfunction "GND_4") (pintype "power_in"))
      (node (ref "UC8") (pin "5") (pinfunction "GND_5") (pintype "power_in"))
      (node (ref "UC9") (pin "4") (pinfunction "GND_4") (pintype "power_in"))
      (node (ref "UC9") (pin "5") (pinfunction "GND_5") (pintype "power_in"))
    )
    (net (code "42") (name "Net-(D1-K)") (class "Default")
      (node (ref "C2") (pin "2") (pinfunction "2_2") (pintype "passive"))
      (node (ref "C3") (pin "1") (pinfunction "1_1") (pintype "passive"))
      (node (ref "D1") (pin "1") (pinfunction "K_1") (pintype "bidirectional"))
      (node (ref "D2") (pin "1") (pinfunction "K_1") (pintype "bidirectional"))
      (node (ref "IC1") (pin "3") (pinfunction "VIN_3") (pintype "input"))
    )
    (net (code "43") (name "Net-(D3-PadPOS)") (class "Default")
      (node (ref "D3") (pin "POS") (pinfunction "POS_POS") (pintype "passive"))
      (node (ref "R7") (pin "2") (pinfunction "2_2") (pintype "passive"))
    )
    (net (code "44") (name "Net-(D4-PadPOS)") (class "Default")
      (node (ref "D4") (pin "POS") (pinfunction "POS_POS") (pintype "passive"))
      (node (ref "R11") (pin "2") (pinfunction "2_2") (pintype "passive"))
    )
    (net (code "45") (name "Net-(J2-Pad2)") (class "Default")
      (node (ref "J2") (pin "2") (pinfunction "2_2") (pintype "passive"))
      (node (ref "R2") (pin "1") (pinfunction "1_1") (pintype "passive"))
    )
    (net (code "46") (name "Net-(J2-Pad3)") (class "Default")
      (node (ref "J2") (pin "3") (pinfunction "3_3") (pintype "passive"))
      (node (ref "R1") (pin "1") (pinfunction "1_1") (pintype "passive"))
    )
    (net (code "47") (name "Net-(J8-Pad1)") (class "Default")
      (node (ref "J8") (pin "1") (pinfunction "1_1") (pintype "passive"))
      (node (ref "UC7") (pin "6") (pinfunction "OUTPUT_6") (pintype "output"))
      (node (ref "UC7") (pin "7") (pinfunction "OUTPUT_7") (pintype "output"))
    )
    (net (code "48") (name "Net-(J8-Pad2)") (class "Default")
      (node (ref "J8") (pin "2") (pinfunction "2_2") (pintype "passive"))
      (node (ref "UC4") (pin "6") (pinfunction "OUTPUT_6") (pintype "output"))
      (node (ref "UC4") (pin "7") (pinfunction "OUTPUT_7") (pintype "output"))
    )
    (net (code "49") (name "Net-(J8-Pad3)") (class "Default")
      (node (ref "J8") (pin "3") (pinfunction "3_3") (pintype "passive"))
      (node (ref "UC1") (pin "6") (pinfunction "OUTPUT_6") (pintype "output"))
      (node (ref "UC1") (pin "7") (pinfunction "OUTPUT_7") (pintype "output"))
    )
    (net (code "50") (name "Net-(J9-Pad1)") (class "Default")
      (node (ref "J9") (pin "1") (pinfunction "1_1") (pintype "passive"))
      (node (ref "UC8") (pin "6") (pinfunction "OUTPUT_6") (pintype "output"))
      (node (ref "UC8") (pin "7") (pinfunction "OUTPUT_7") (pintype "output"))
    )
    (net (code "51") (name "Net-(J9-Pad2)") (class "Default")
      (node (ref "J9") (pin "2") (pinfunction "2_2") (pintype "passive"))
      (node (ref "UC5") (pin "6") (pinfunction "OUTPUT_6") (pintype "output"))
      (node (ref "UC5") (pin "7") (pinfunction "OUTPUT_7") (pintype "output"))
    )
    (net (code "52") (name "Net-(J9-Pad3)") (class "Default")
      (node (ref "J9") (pin "3") (pinfunction "3_3") (pintype "passive"))
      (node (ref "UC2") (pin "6") (pinfunction "OUTPUT_6") (pintype "output"))
      (node (ref "UC2") (pin "7") (pinfunction "OUTPUT_7") (pintype "output"))
    )
    (net (code "53") (name "Net-(J10-Pad1)") (class "Default")
      (node (ref "J10") (pin "1") (pinfunction "1_1") (pintype "passive"))
      (node (ref "UC9") (pin "6") (pinfunction "OUTPUT_6") (pintype "output"))
      (node (ref "UC9") (pin "7") (pinfunction "OUTPUT_7") (pintype "output"))
    )
    (net (code "54") (name "Net-(J10-Pad2)") (class "Default")
      (node (ref "J10") (pin "2") (pinfunction "2_2") (pintype "passive"))
      (node (ref "UC6") (pin "6") (pinfunction "OUTPUT_6") (pintype "output"))
      (node (ref "UC6") (pin "7") (pinfunction "OUTPUT_7") (pintype "output"))
    )
    (net (code "55") (name "Net-(J10-Pad3)") (class "Default")
      (node (ref "J10") (pin "3") (pinfunction "3_3") (pintype "passive"))
      (node (ref "UC3") (pin "6") (pinfunction "OUTPUT_6") (pintype "output"))
      (node (ref "UC3") (pin "7") (pinfunction "OUTPUT_7") (pintype "output"))
    )
    (net (code "56") (name "Net-(Q1-2)") (class "Default")
      (node (ref "C5") (pin "2") (pinfunction "2_2") (pintype "passive"))
      (node (ref "Q1") (pin "3") (pinfunction "2_3") (pintype "passive"))
      (node (ref "STM1") (pin "5") (pinfunction "PD0-OSC_IN_5") (pintype "input"))
    )
    (net (code "57") (name "Net-(STM1-BOOT0)") (class "Default")
      (node (ref "R12") (pin "2") (pinfunction "2_2") (pintype "passive"))
      (node (ref "STM1") (pin "60") (pinfunction "BOOT0_60") (pintype "input"))
      (node (ref "SW1") (pin "2") (pinfunction "2_2") (pintype "passive"))
    )
    (net (code "58") (name "Net-(STM1-NRST)") (class "Default")
      (node (ref "C11") (pin "1") (pinfunction "1_1") (pintype "passive"))
      (node (ref "STM1") (pin "7") (pinfunction "NRST_7") (pintype "input"))
      (node (ref "SW2") (pin "1") (pinfunction "1_1") (pintype "passive"))
    )
    (net (code "59") (name "Net-(STM1-PD1_OSC_OUT)") (class "Default")
      (node (ref "C1") (pin "2") (pinfunction "2_2") (pintype "passive"))
      (node (ref "Q1") (pin "1") (pinfunction "1_1") (pintype "passive"))
      (node (ref "STM1") (pin "6") (pinfunction "PD1_OSC_OUT_6") (pintype "output"))
    )
    (net (code "60") (name "Net-(U1-D+)") (class "Default")
      (node (ref "R4") (pin "1") (pinfunction "1_1") (pintype "passive"))
      (node (ref "R5") (pin "1") (pinfunction "1_1") (pintype "passive"))
      (node (ref "U1") (pin "3") (pinfunction "D+_3") (pintype "bidirectional"))
    )
    (net (code "61") (name "Net-(U1-D-)") (class "Default")
      (node (ref "R6") (pin "1") (pinfunction "1_1") (pintype "passive"))
      (node (ref "U1") (pin "2") (pinfunction "D-_2") (pintype "bidirectional"))
    )
    (net (code "62") (name "Net-(U2-AD0)") (class "Default")
      (node (ref "R19") (pin "2") (pinfunction "2_2") (pintype "passive"))
      (node (ref "U2") (pin "9") (pinfunction "AD0_9") (pintype "passive"))
    )
    (net (code "63") (name "Net-(U2-CPOUT)") (class "Default")
      (node (ref "C20") (pin "2") (pinfunction "2_2") (pintype "passive"))
      (node (ref "U2") (pin "20") (pinfunction "CPOUT_20") (pintype "passive"))
    )
    (net (code "64") (name "Net-(U2-REGOUT)") (class "Default")
      (node (ref "C18") (pin "1") (pinfunction "1_1") (pintype "passive"))
      (node (ref "U2") (pin "10") (pinfunction "REGOUT_10") (pintype "passive"))
    )
    (net (code "65") (name "VBAT") (class "Default")
      (node (ref "C12") (pin "1") (pinfunction "1_1") (pintype "passive"))
      (node (ref "C13") (pin "2") (pinfunction "2_2") (pintype "passive"))
      (node (ref "C14") (pin "1") (pinfunction "1_1") (pintype "passive"))
      (node (ref "C15") (pin "1") (pinfunction "1_1") (pintype "passive"))
      (node (ref "C16") (pin "1") (pinfunction "1_1") (pintype "passive"))
      (node (ref "C17") (pin "2") (pinfunction "2_2") (pintype "passive"))
      (node (ref "D1") (pin "2") (pinfunction "A_2") (pintype "bidirectional"))
      (node (ref "R10") (pin "1") (pinfunction "1_1") (pintype "passive"))
      (node (ref "UC1") (pin "1") (pinfunction "VDD_1") (pintype "power_in"))
      (node (ref "UC1") (pin "8") (pinfunction "VDD_8") (pintype "power_in"))
      (node (ref "UC2") (pin "1") (pinfunction "VDD_1") (pintype "power_in"))
      (node (ref "UC2") (pin "8") (pinfunction "VDD_8") (pintype "power_in"))
      (node (ref "UC3") (pin "1") (pinfunction "VDD_1") (pintype "power_in"))
      (node (ref "UC3") (pin "8") (pinfunction "VDD_8") (pintype "power_in"))
      (node (ref "UC4") (pin "1") (pinfunction "VDD_1") (pintype "power_in"))
      (node (ref "UC4") (pin "8") (pinfunction "VDD_8") (pintype "power_in"))
      (node (ref "UC5") (pin "1") (pinfunction "VDD_1") (pintype "power_in"))
      (node (ref "UC5") (pin "8") (pinfunction "VDD_8") (pintype "power_in"))
      (node (ref "UC6") (pin "1") (pinfunction "VDD_1") (pintype "power_in"))
      (node (ref "UC6") (pin "8") (pinfunction "VDD_8") (pintype "power_in"))
      (node (ref "UC7") (pin "1") (pinfunction "VDD_1") (pintype "power_in"))
      (node (ref "UC7") (pin "8") (pinfunction "VDD_8") (pintype "power_in"))
      (node (ref "UC8") (pin "1") (pinfunction "VDD_1") (pintype "power_in"))
      (node (ref "UC8") (pin "8") (pinfunction "VDD_8") (pintype "power_in"))
      (node (ref "UC9") (pin "1") (pinfunction "VDD_1") (pintype "power_in"))
      (node (ref "UC9") (pin "8") (pinfunction "VDD_8") (pintype "power_in"))
    )
    (net (code "66") (name "VUSB") (class "Default")
      (node (ref "D2") (pin "2") (pinfunction "A_2") (pintype "bidirectional"))
      (node (ref "U1") (pin "1") (pinfunction "VBUS_1") (pintype "power_in"))
    )
    (net (code "67") (name "unconnected-(STM1-PA15-Pad50)") (class "Default")
      (node (ref "STM1") (pin "50") (pinfunction "PA15_50") (pintype "bidirectional"))
    )
    (net (code "68") (name "unconnected-(STM1-PB3-Pad55)") (class "Default")
      (node (ref "STM1") (pin "55") (pinfunction "PB3_55") (pintype "bidirectional"))
    )
    (net (code "69") (name "unconnected-(STM1-PB4-Pad56)") (class "Default")
      (node (ref "STM1") (pin "56") (pinfunction "PB4_56") (pintype "bidirectional"))
    )
    (net (code "70") (name "unconnected-(STM1-PC3-Pad11)") (class "Default")
      (node (ref "STM1") (pin "11") (pinfunction "PC3_11") (pintype "bidirectional"))
    )
    (net (code "71") (name "unconnected-(STM1-PC4-Pad24)") (class "Default")
      (node (ref "STM1") (pin "24") (pinfunction "PC4_24") (pintype "bidirectional"))
    )
    (net (code "72") (name "unconnected-(STM1-PC5-Pad25)") (class "Default")
      (node (ref "STM1") (pin "25") (pinfunction "PC5_25") (pintype "bidirectional"))
    )
    (net (code "73") (name "unconnected-(STM1-PC12-Pad53)") (class "Default")
      (node (ref "STM1") (pin "53") (pinfunction "PC12_53") (pintype "bidirectional"))
    )
    (net (code "74") (name "unconnected-(STM1-PC13-TAMPER-RTC-Pad2)") (class "Default")
      (node (ref "STM1") (pin "2") (pinfunction "PC13-TAMPER-RTC_2") (pintype "bidirectional"))
    )
    (net (code "75") (name "unconnected-(STM1-PC14-OSC32_IN-Pad3)") (class "Default")
      (node (ref "STM1") (pin "3") (pinfunction "PC14-OSC32_IN_3") (pintype "bidirectional"))
    )
    (net (code "76") (name "unconnected-(STM1-PC15-OSC32_OUT-Pad4)") (class "Default")
      (node (ref "STM1") (pin "4") (pinfunction "PC15-OSC32_OUT_4") (pintype "bidirectional"))
    )
    (net (code "77") (name "unconnected-(STM1-PD2-Pad54)") (class "Default")
      (node (ref "STM1") (pin "54") (pinfunction "PD2_54") (pintype "bidirectional"))
    )
    (net (code "78") (name "unconnected-(U1-ID-Pad4)") (class "Default")
      (node (ref "U1") (pin "4") (pinfunction "ID_4") (pintype "bidirectional"))
    )
    (net (code "79") (name "unconnected-(U2-AUX_CL-Pad7)") (class "Default")
      (node (ref "U2") (pin "7") (pinfunction "AUX_CL_7") (pintype "passive"))
    )
    (net (code "80") (name "unconnected-(U2-AUX_DA-Pad6)") (class "Default")
      (node (ref "U2") (pin "6") (pinfunction "AUX_DA_6") (pintype "passive"))
    )
    (net (code "81") (name "unconnected-(U2-CLKIN-Pad1)") (class "Default")
      (node (ref "U2") (pin "1") (pinfunction "CLKIN_1") (pintype "passive"))
    )
    (net (code "82") (name "unconnected-(U2-INT-Pad12)") (class "Default")
      (node (ref "U2") (pin "12") (pinfunction "INT_12") (pintype "passive"))
    )
    (net (code "83") (name "unconnected-(UC1-NC-Pad3)") (class "Default")
      (node (ref "UC1") (pin "3") (pinfunction "NC_3") (pintype "bidirectional"))
    )
    (net (code "84") (name "unconnected-(UC2-NC-Pad3)") (class "Default")
      (node (ref "UC2") (pin "3") (pinfunction "NC_3") (pintype "bidirectional"))
    )
    (net (code "85") (name "unconnected-(UC3-NC-Pad3)") (class "Default")
      (node (ref "UC3") (pin "3") (pinfunction "NC_3") (pintype "bidirectional"))
    )
    (net (code "86") (name "unconnected-(UC4-NC-Pad3)") (class "Default")
      (node (ref "UC4") (pin "3") (pinfunction "NC_3") (pintype "bidirectional"))
    )
    (net (code "87") (name "unconnected-(UC5-NC-Pad3)") (class "Default")
      (node (ref "UC5") (pin "3") (pinfunction "NC_3") (pintype "bidirectional"))
    )
    (net (code "88") (name "unconnected-(UC6-NC-Pad3)") (class "Default")
      (node (ref "UC6") (pin "3") (pinfunction "NC_3") (pintype "bidirectional"))
    )
    (net (code "89") (name "unconnected-(UC7-NC-Pad3)") (class "Default")
      (node (ref "UC7") (pin "3") (pinfunction "NC_3") (pintype "bidirectional"))
    )
    (net (code "90") (name "unconnected-(UC8-NC-Pad3)") (class "Default")
      (node (ref "UC8") (pin "3") (pinfunction "NC_3") (pintype "bidirectional"))
    )
    (net (code "91") (name "unconnected-(UC9-NC-Pad3)") (class "Default")
      (node (ref "UC9") (pin "3") (pinfunction "NC_3") (pintype "bidirectional"))
    )
  )
)
